# EasyEDA_Pro_EXPORT.net
KiCad netlist of a schematic drawn in EasyEDA Pro
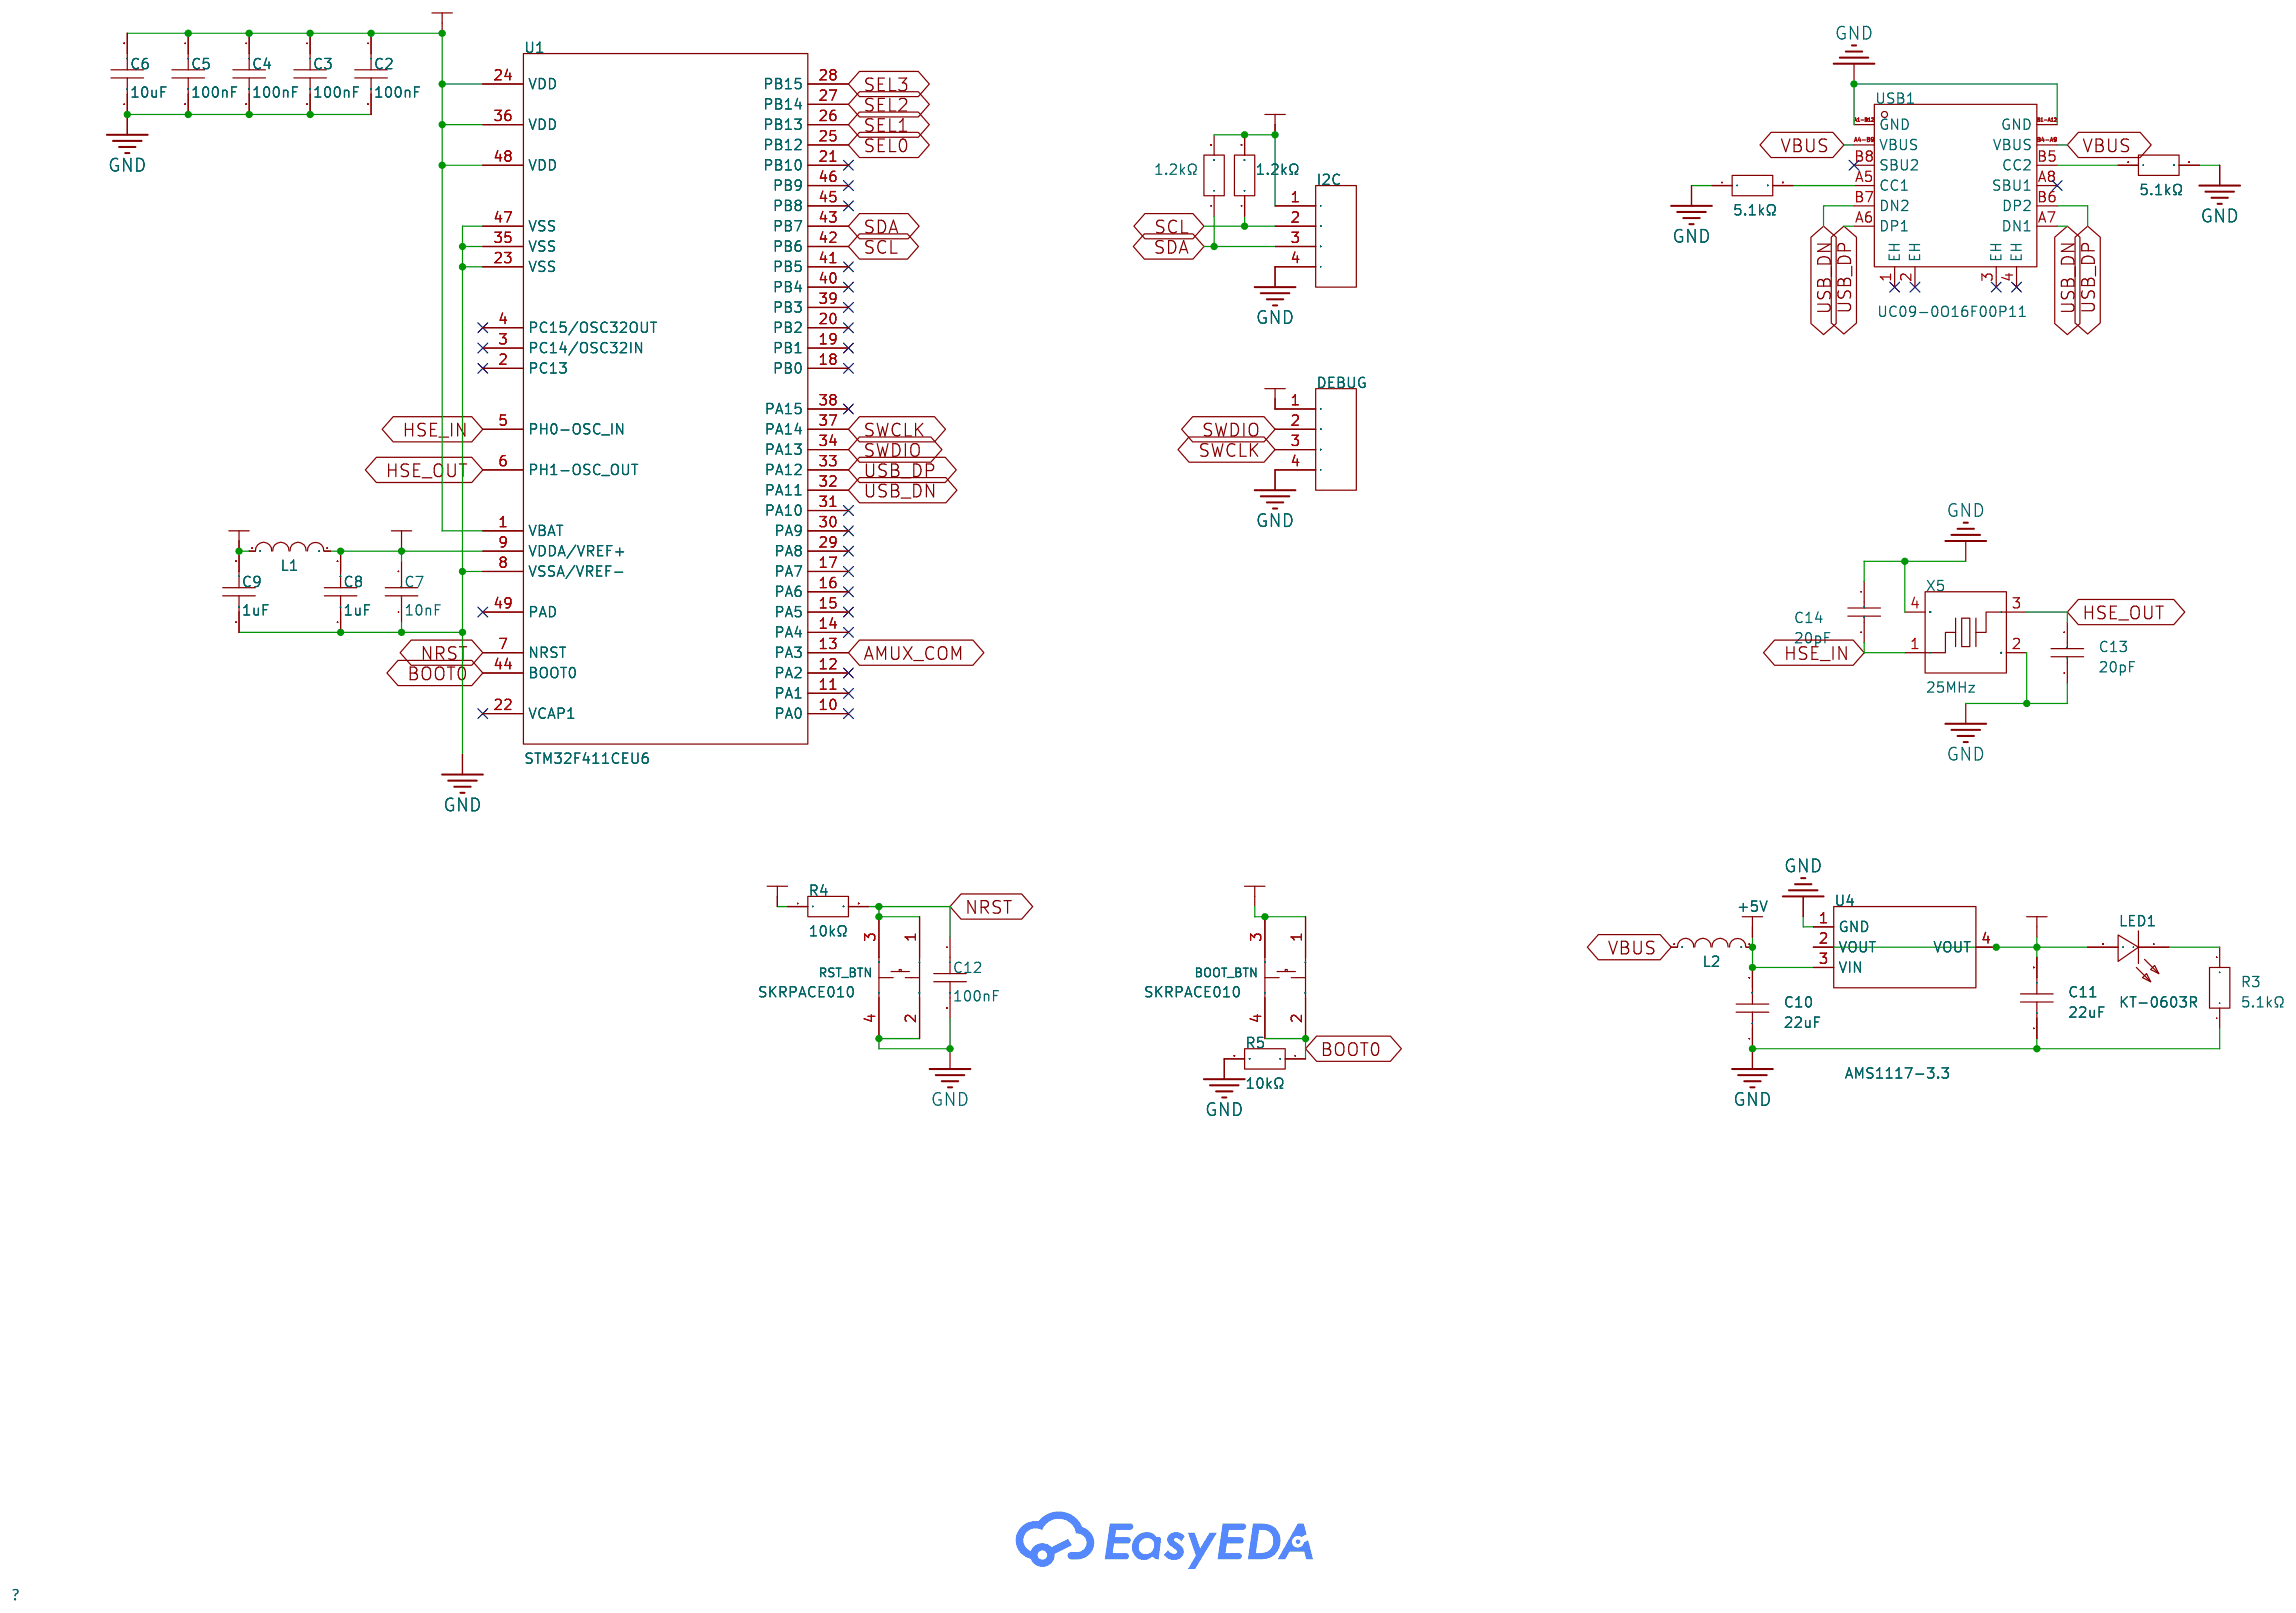
[diagram p0: microcontroller]
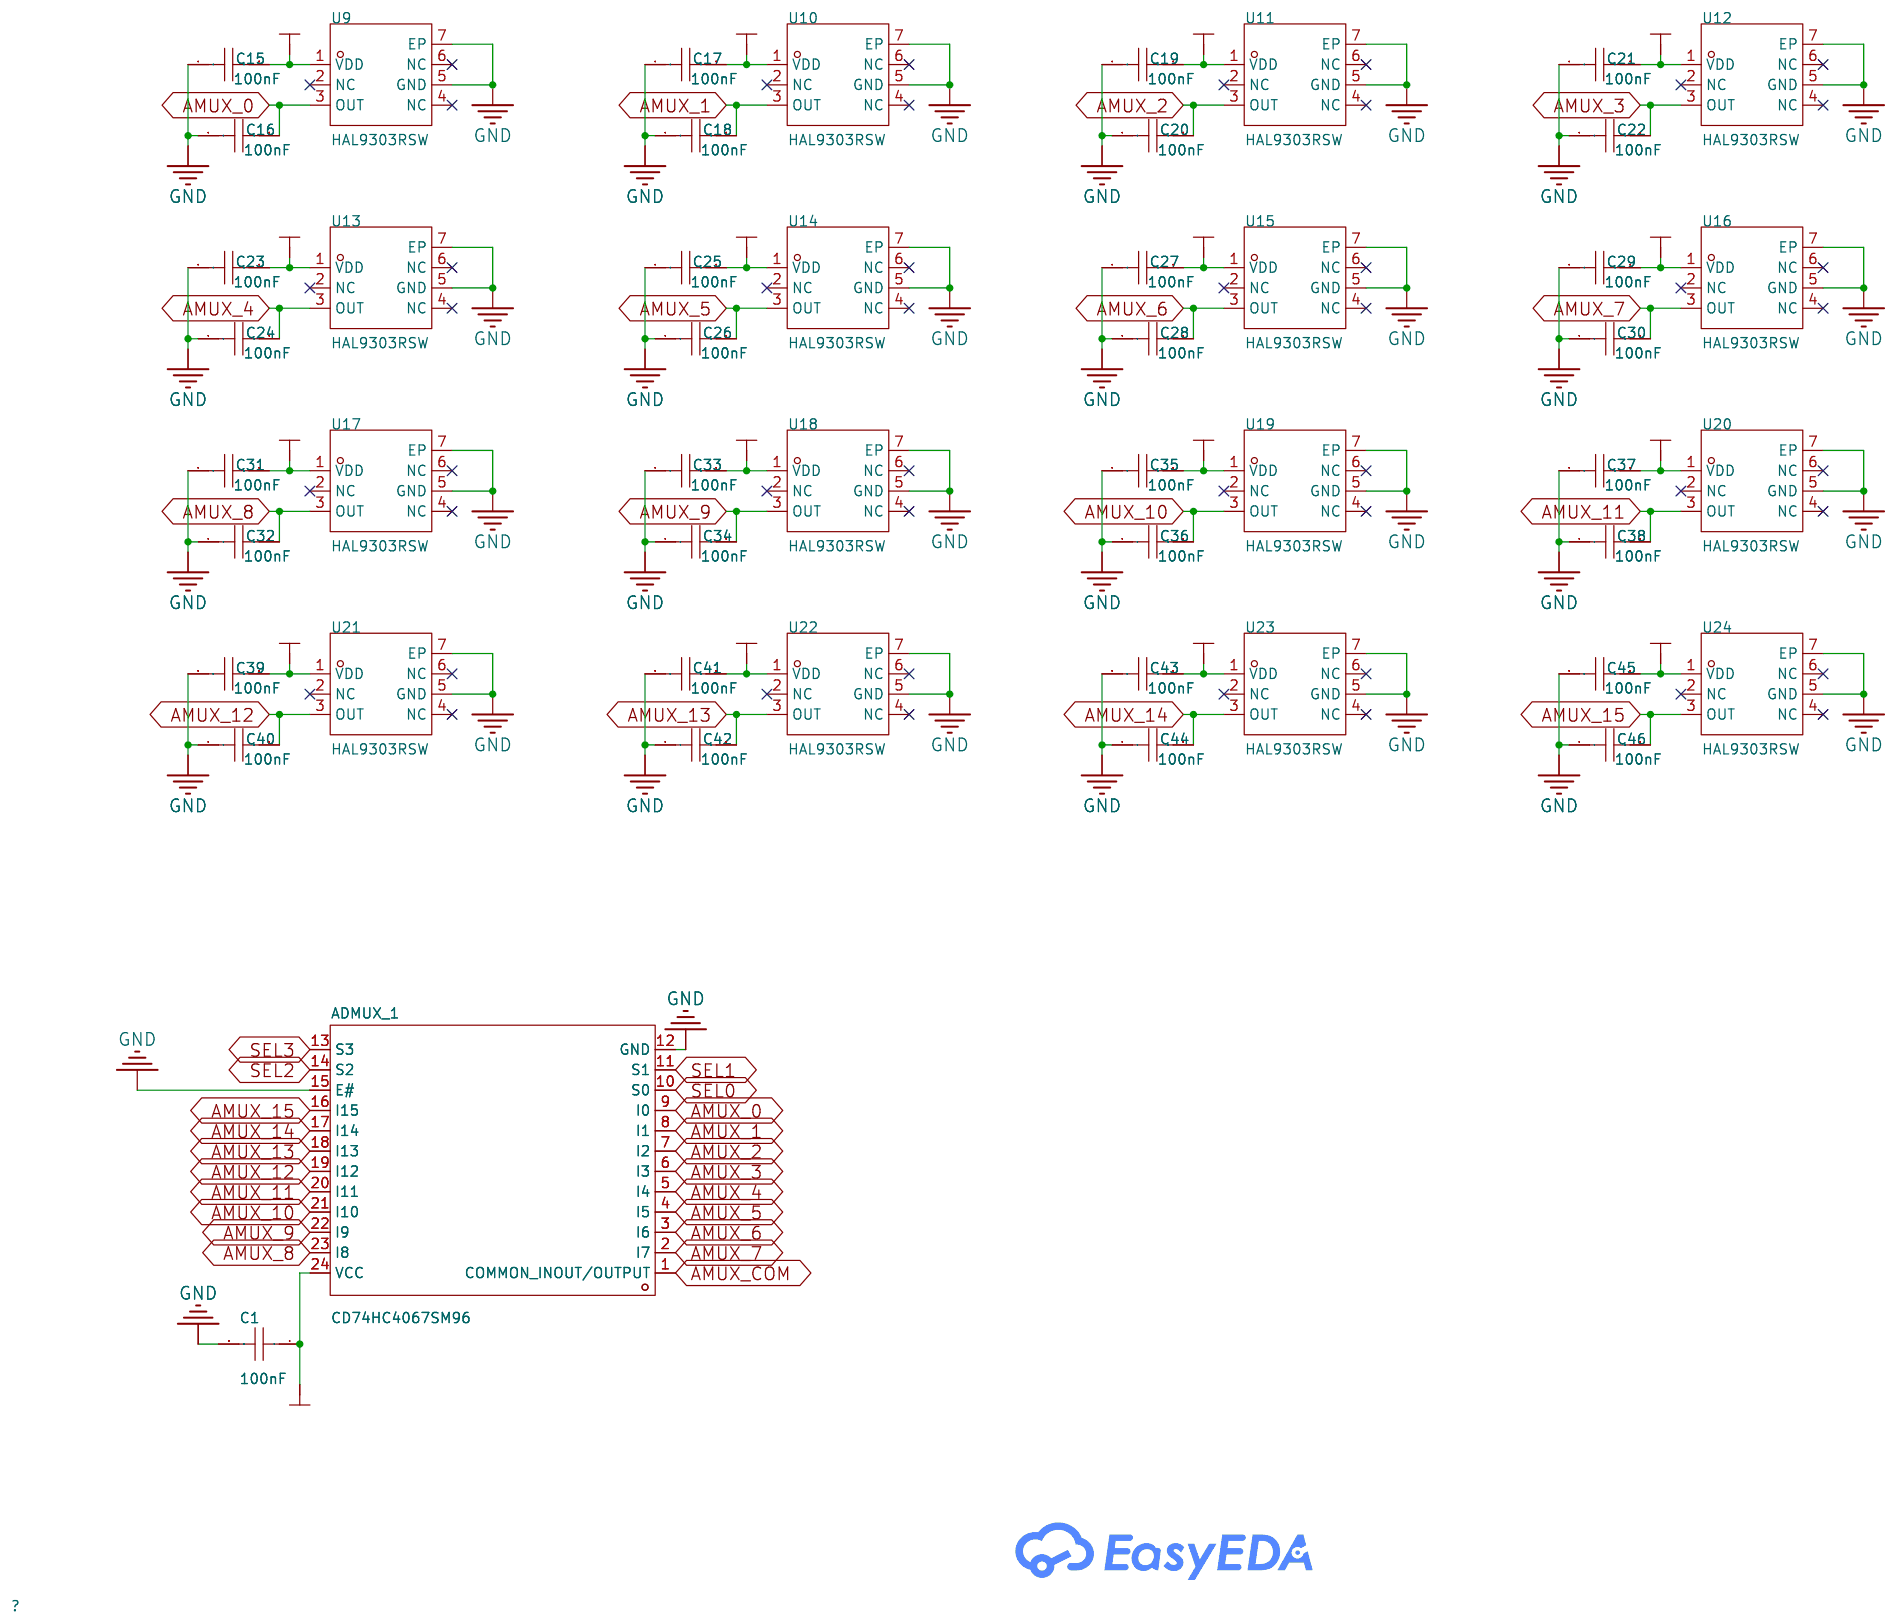
[diagram p1: buttons]

(export (version "E")
  (design (tool "Eeschema 10.0.6"))
  (components
    (comp (ref "BOOT_BTN")
      (value "SKRPACE010")
      (footprint "easyedapro:KEY-SMD_4P-L4.2-W3.2-P2.20-LS4.6")
      (fields (field (name "Manufacturer") "ALPSALPINE(阿尔卑斯阿尔派)"))
      (libsource (lib "easyedapro") (part "SKRPACE010"))
    )
    (comp (ref "C2")
      (value "100nF")
      (footprint "easyedapro:C0201")
      (description "Capacitance:100nF Tolerance:±10% Tolerance:±10% Voltage Rating:16V Temperature Coefficient:X7R")
      (fields
        (field (name "Manufacturer Part") "TCC0201X7R104K160ZT")
        (field (name "Manufacturer") "CCTC(三环)")
      )
      (libsource (lib "easyedapro") (part "TCC0201X7R104K160ZT"))
    )
    (comp (ref "C3")
      (value "100nF")
      (footprint "easyedapro:C0201")
      (description "Capacitance:100nF Tolerance:±10% Tolerance:±10% Voltage Rating:16V Temperature Coefficient:X7R")
      (fields
        (field (name "Manufacturer Part") "TCC0201X7R104K160ZT")
        (field (name "Manufacturer") "CCTC(三环)")
      )
      (libsource (lib "easyedapro") (part "TCC0201X7R104K160ZT"))
    )
    (comp (ref "C4")
      (value "100nF")
      (footprint "easyedapro:C0201")
      (description "Capacitance:100nF Tolerance:±10% Tolerance:±10% Voltage Rating:16V Temperature Coefficient:X7R")
      (fields
        (field (name "Manufacturer Part") "TCC0201X7R104K160ZT")
        (field (name "Manufacturer") "CCTC(三环)")
      )
      (libsource (lib "easyedapro") (part "TCC0201X7R104K160ZT"))
    )
    (comp (ref "C5")
      (value "100nF")
      (footprint "easyedapro:C0201")
      (description "Capacitance:100nF Tolerance:±10% Tolerance:±10% Voltage Rating:16V Temperature Coefficient:X7R")
      (fields
        (field (name "Manufacturer Part") "TCC0201X7R104K160ZT")
        (field (name "Manufacturer") "CCTC(三环)")
      )
      (libsource (lib "easyedapro") (part "TCC0201X7R104K160ZT"))
    )
    (comp (ref "C6")
      (value "10uF")
      (footprint "easyedapro:C1206")
      (description "Capacitance:10uF Tolerance:±10% Tolerance:±10% Voltage Rating:35V Temperature Coefficient:X7R")
      (fields
        (field (name "Manufacturer Part") "HGC1206R7106K350NSPJ")
        (field (name "Manufacturer") "Chinocera(华瓷)")
      )
      (libsource (lib "easyedapro") (part "HGC1206R7106K350NSPJ"))
    )
    (comp (ref "C7")
      (value "10nF")
      (footprint "easyedapro:C0402")
      (description "Capacitance:10nF Tolerance:±10% Tolerance:±10% Voltage Rating:50V Temperature Coefficient:X7R")
      (fields (field (name "Manufacturer Part") "0402B103K500NT") (field (name "Manufacturer") "FH(风华)"))
      (libsource (lib "easyedapro") (part "0402B103K500NT"))
    )
    (comp (ref "C8")
      (value "1uF")
      (footprint "easyedapro:C0402")
      (description "Capacitance:1uF Tolerance:±10% Tolerance:±10% Voltage Rating:50V Temperature Coefficient:X5R")
      (fields
        (field (name "Manufacturer Part") "TCC0402X5R105K500AT")
        (field (name "Manufacturer") "CCTC(三环)")
      )
      (libsource (lib "easyedapro") (part "TCC0402X5R105K500AT"))
    )
    (comp (ref "C9")
      (value "1uF")
      (footprint "easyedapro:C0402")
      (description "Capacitance:1uF Tolerance:±10% Tolerance:±10% Voltage Rating:50V Temperature Coefficient:X5R")
      (fields
        (field (name "Manufacturer Part") "TCC0402X5R105K500AT")
        (field (name "Manufacturer") "CCTC(三环)")
      )
      (libsource (lib "easyedapro") (part "TCC0402X5R105K500AT"))
    )
    (comp (ref "C10")
      (value "22uF")
      (footprint "easyedapro:C1206")
      (description "Capacitance:22uF Tolerance:±10% Tolerance:±10% Voltage Rating:16V Temperature Coefficient:X7R")
      (fields
        (field (name "Manufacturer Part") "TCC1206X7R226K160HT")
        (field (name "Manufacturer") "CCTC(三环)")
      )
      (libsource (lib "easyedapro") (part "TCC1206X7R226K160HT"))
    )
    (comp (ref "C11")
      (value "22uF")
      (footprint "easyedapro:C1206")
      (description "Capacitance:22uF Tolerance:±10% Tolerance:±10% Voltage Rating:16V Temperature Coefficient:X7R")
      (fields
        (field (name "Manufacturer Part") "TCC1206X7R226K160HT")
        (field (name "Manufacturer") "CCTC(三环)")
      )
      (libsource (lib "easyedapro") (part "TCC1206X7R226K160HT"))
    )
    (comp (ref "C12")
      (value "100nF")
      (footprint "easyedapro:C0201")
      (description "Capacitance:100nF Tolerance:±10% Tolerance:±10% Voltage Rating:16V Temperature Coefficient:X7R")
      (fields
        (field (name "Manufacturer Part") "TCC0201X7R104K160ZT")
        (field (name "Manufacturer") "CCTC(三环)")
      )
      (libsource (lib "easyedapro") (part "TCC0201X7R104K160ZT"))
    )
    (comp (ref "C13")
      (value "20pF")
      (footprint "easyedapro:C0402")
      (fields (field (name "Manufacturer Part") "0402CG200J500NT") (field (name "Manufacturer") "FH(风华)"))
      (libsource (lib "easyedapro") (part "0402CG200J500NT"))
    )
    (comp (ref "C14")
      (value "20pF")
      (footprint "easyedapro:C0402")
      (fields (field (name "Manufacturer Part") "0402CG200J500NT") (field (name "Manufacturer") "FH(风华)"))
      (libsource (lib "easyedapro") (part "0402CG200J500NT"))
    )
    (comp (ref "DEBUG")
      (value "~")
      (footprint "easyedapro:4 Pin Header")
      (libsource (lib "easyedapro") (part "4 Pin Header"))
    )
    (comp (ref "I2C")
      (value "~")
      (footprint "easyedapro:4 Pin Header")
      (libsource (lib "easyedapro") (part "4 Pin Header"))
    )
    (comp (ref "L1")
      (value "BLM18AG121SN1D")
      (footprint "easyedapro:L0603")
      (fields (field (name "Manufacturer") "muRata(村田)"))
      (libsource (lib "easyedapro") (part "BLM18AG121SN1D"))
    )
    (comp (ref "L2")
      (value "BLM18AG121SN1D")
      (footprint "easyedapro:L0603")
      (fields (field (name "Manufacturer") "muRata(村田)"))
      (libsource (lib "easyedapro") (part "BLM18AG121SN1D"))
    )
    (comp (ref "LED1")
      (value "KT-0603R")
      (footprint "easyedapro:LED0603-RD")
      (fields (field (name "Manufacturer") "KENTO"))
      (libsource (lib "easyedapro") (part "KT-0603R"))
    )
    (comp (ref "R1")
      (value "5.1kΩ")
      (footprint "easyedapro:R0402")
      (fields (field (name "Manufacturer Part") "FRC0402J512 TS") (field (name "Manufacturer") "FOJAN(富捷)"))
      (libsource (lib "easyedapro") (part "FRC0402J512 TS"))
    )
    (comp (ref "R2")
      (value "5.1kΩ")
      (footprint "easyedapro:R0402")
      (fields (field (name "Manufacturer Part") "FRC0402J512 TS") (field (name "Manufacturer") "FOJAN(富捷)"))
      (libsource (lib "easyedapro") (part "FRC0402J512 TS"))
    )
    (comp (ref "R3")
      (value "5.1kΩ")
      (footprint "easyedapro:R0402")
      (fields (field (name "Manufacturer Part") "FRC0402J512 TS") (field (name "Manufacturer") "FOJAN(富捷)"))
      (libsource (lib "easyedapro") (part "FRC0402J512 TS"))
    )
    (comp (ref "R4")
      (value "10kΩ")
      (footprint "easyedapro:R0805")
      (fields
        (field (name "Manufacturer Part") "HoAR0805-1/8W-10KR-1%-TCR25")
        (field (name "Manufacturer") "Milliohm(毫欧)")
      )
      (libsource (lib "easyedapro") (part "HOAR0805-1/8W-10KR-1%-TCR25"))
    )
    (comp (ref "R5")
      (value "10kΩ")
      (footprint "easyedapro:R0805")
      (fields
        (field (name "Manufacturer Part") "HoAR0805-1/8W-10KR-1%-TCR25")
        (field (name "Manufacturer") "Milliohm(毫欧)")
      )
      (libsource (lib "easyedapro") (part "HOAR0805-1/8W-10KR-1%-TCR25"))
    )
    (comp (ref "R6")
      (value "1.2kΩ")
      (footprint "easyedapro:R0201")
      (fields (field (name "Manufacturer Part") "AC0201FR-071K2L") (field (name "Manufacturer") "YAGEO(国巨)"))
      (libsource (lib "easyedapro") (part "AC0201FR-071K2L"))
    )
    (comp (ref "R7")
      (value "1.2kΩ")
      (footprint "easyedapro:R0201")
      (fields (field (name "Manufacturer Part") "AC0201FR-071K2L") (field (name "Manufacturer") "YAGEO(国巨)"))
      (libsource (lib "easyedapro") (part "AC0201FR-071K2L"))
    )
    (comp (ref "RST_BTN")
      (value "SKRPACE010")
      (footprint "easyedapro:KEY-SMD_4P-L4.2-W3.2-P2.20-LS4.6")
      (fields (field (name "Manufacturer") "ALPSALPINE(阿尔卑斯阿尔派)"))
      (libsource (lib "easyedapro") (part "SKRPACE010"))
    )
    (comp (ref "U1")
      (value "STM32F411CEU6")
      (footprint "easyedapro:UFQFPN-48_L7.0-W7.0-P0.50-BL-EP")
      (fields (field (name "Manufacturer") "ST(意法半导体)"))
      (libsource (lib "easyedapro") (part "STM32F411CEU6"))
    )
    (comp (ref "U4")
      (value "AMS1117-3.3")
      (footprint "easyedapro:SOT-223-3_L6.5-W3.4-P2.30-LS7.0-BR")
      (fields (field (name "Manufacturer") "AMS"))
      (libsource (lib "easyedapro") (part "AMS1117-3.3"))
    )
    (comp (ref "USB1")
      (value "UC09-0O16F00P11")
      (footprint "easyedapro:USB-C-SMD_UC09-0O16F00P11")
      (fields (field (name "Manufacturer") "BXCONN(宝讯)"))
      (libsource (lib "easyedapro") (part "UC09-0O16F00P11"))
    )
    (comp (ref "X5")
      (value "25MHz")
      (footprint "easyedapro:CRYSTAL-SMD_4P-L3.2-W2.5-BL")
      (fields (field (name "Manufacturer Part") "S3225000271060C3") (field (name "Manufacturer") "JGHC(晶光华)"))
      (libsource (lib "easyedapro") (part "S3225000271060C3"))
    )
    (comp (ref "ADMUX_1")
      (value "CD74HC4067SM96")
      (footprint "easyedapro:SSOP-24_L8.1-W5.3-P0.65-LS7.8-BL")
      (fields (field (name "Manufacturer") "TI(德州仪器)"))
      (libsource (lib "easyedapro") (part "CD74HC4067SM96"))
    )
    (comp (ref "C1")
      (value "100nF")
      (footprint "easyedapro:C0201")
      (description "Capacitance:100nF Tolerance:±10% Tolerance:±10% Voltage Rating:16V Temperature Coefficient:X7R")
      (fields
        (field (name "Manufacturer Part") "TCC0201X7R104K160ZT")
        (field (name "Manufacturer") "CCTC(三环)")
      )
      (libsource (lib "easyedapro") (part "TCC0201X7R104K160ZT"))
    )
    (comp (ref "C15")
      (value "100nF")
      (footprint "easyedapro:C0201")
      (description "Capacitance:100nF Tolerance:±10% Tolerance:±10% Voltage Rating:16V Temperature Coefficient:X7R")
      (fields
        (field (name "Manufacturer Part") "TCC0201X7R104K160ZT")
        (field (name "Manufacturer") "CCTC(三环)")
      )
      (libsource (lib "easyedapro") (part "TCC0201X7R104K160ZT"))
    )
    (comp (ref "C16")
      (value "100nF")
      (footprint "easyedapro:C0201")
      (description "Capacitance:100nF Tolerance:±10% Tolerance:±10% Voltage Rating:16V Temperature Coefficient:X7R")
      (fields
        (field (name "Manufacturer Part") "TCC0201X7R104K160ZT")
        (field (name "Manufacturer") "CCTC(三环)")
      )
      (libsource (lib "easyedapro") (part "TCC0201X7R104K160ZT"))
    )
    (comp (ref "C17")
      (value "100nF")
      (footprint "easyedapro:C0201")
      (description "Capacitance:100nF Tolerance:±10% Tolerance:±10% Voltage Rating:16V Temperature Coefficient:X7R")
      (fields
        (field (name "Manufacturer Part") "TCC0201X7R104K160ZT")
        (field (name "Manufacturer") "CCTC(三环)")
      )
      (libsource (lib "easyedapro") (part "TCC0201X7R104K160ZT"))
    )
    (comp (ref "C18")
      (value "100nF")
      (footprint "easyedapro:C0201")
      (description "Capacitance:100nF Tolerance:±10% Tolerance:±10% Voltage Rating:16V Temperature Coefficient:X7R")
      (fields
        (field (name "Manufacturer Part") "TCC0201X7R104K160ZT")
        (field (name "Manufacturer") "CCTC(三环)")
      )
      (libsource (lib "easyedapro") (part "TCC0201X7R104K160ZT"))
    )
    (comp (ref "C19")
      (value "100nF")
      (footprint "easyedapro:C0201")
      (description "Capacitance:100nF Tolerance:±10% Tolerance:±10% Voltage Rating:16V Temperature Coefficient:X7R")
      (fields
        (field (name "Manufacturer Part") "TCC0201X7R104K160ZT")
        (field (name "Manufacturer") "CCTC(三环)")
      )
      (libsource (lib "easyedapro") (part "TCC0201X7R104K160ZT"))
    )
    (comp (ref "C20")
      (value "100nF")
      (footprint "easyedapro:C0201")
      (description "Capacitance:100nF Tolerance:±10% Tolerance:±10% Voltage Rating:16V Temperature Coefficient:X7R")
      (fields
        (field (name "Manufacturer Part") "TCC0201X7R104K160ZT")
        (field (name "Manufacturer") "CCTC(三环)")
      )
      (libsource (lib "easyedapro") (part "TCC0201X7R104K160ZT"))
    )
    (comp (ref "C21")
      (value "100nF")
      (footprint "easyedapro:C0201")
      (description "Capacitance:100nF Tolerance:±10% Tolerance:±10% Voltage Rating:16V Temperature Coefficient:X7R")
      (fields
        (field (name "Manufacturer Part") "TCC0201X7R104K160ZT")
        (field (name "Manufacturer") "CCTC(三环)")
      )
      (libsource (lib "easyedapro") (part "TCC0201X7R104K160ZT"))
    )
    (comp (ref "C22")
      (value "100nF")
      (footprint "easyedapro:C0201")
      (description "Capacitance:100nF Tolerance:±10% Tolerance:±10% Voltage Rating:16V Temperature Coefficient:X7R")
      (fields
        (field (name "Manufacturer Part") "TCC0201X7R104K160ZT")
        (field (name "Manufacturer") "CCTC(三环)")
      )
      (libsource (lib "easyedapro") (part "TCC0201X7R104K160ZT"))
    )
    (comp (ref "C23")
      (value "100nF")
      (footprint "easyedapro:C0201")
      (description "Capacitance:100nF Tolerance:±10% Tolerance:±10% Voltage Rating:16V Temperature Coefficient:X7R")
      (fields
        (field (name "Manufacturer Part") "TCC0201X7R104K160ZT")
        (field (name "Manufacturer") "CCTC(三环)")
      )
      (libsource (lib "easyedapro") (part "TCC0201X7R104K160ZT"))
    )
    (comp (ref "C24")
      (value "100nF")
      (footprint "easyedapro:C0201")
      (description "Capacitance:100nF Tolerance:±10% Tolerance:±10% Voltage Rating:16V Temperature Coefficient:X7R")
      (fields
        (field (name "Manufacturer Part") "TCC0201X7R104K160ZT")
        (field (name "Manufacturer") "CCTC(三环)")
      )
      (libsource (lib "easyedapro") (part "TCC0201X7R104K160ZT"))
    )
    (comp (ref "C25")
      (value "100nF")
      (footprint "easyedapro:C0201")
      (description "Capacitance:100nF Tolerance:±10% Tolerance:±10% Voltage Rating:16V Temperature Coefficient:X7R")
      (fields
        (field (name "Manufacturer Part") "TCC0201X7R104K160ZT")
        (field (name "Manufacturer") "CCTC(三环)")
      )
      (libsource (lib "easyedapro") (part "TCC0201X7R104K160ZT"))
    )
    (comp (ref "C26")
      (value "100nF")
      (footprint "easyedapro:C0201")
      (description "Capacitance:100nF Tolerance:±10% Tolerance:±10% Voltage Rating:16V Temperature Coefficient:X7R")
      (fields
        (field (name "Manufacturer Part") "TCC0201X7R104K160ZT")
        (field (name "Manufacturer") "CCTC(三环)")
      )
      (libsource (lib "easyedapro") (part "TCC0201X7R104K160ZT"))
    )
    (comp (ref "C27")
      (value "100nF")
      (footprint "easyedapro:C0201")
      (description "Capacitance:100nF Tolerance:±10% Tolerance:±10% Voltage Rating:16V Temperature Coefficient:X7R")
      (fields
        (field (name "Manufacturer Part") "TCC0201X7R104K160ZT")
        (field (name "Manufacturer") "CCTC(三环)")
      )
      (libsource (lib "easyedapro") (part "TCC0201X7R104K160ZT"))
    )
    (comp (ref "C28")
      (value "100nF")
      (footprint "easyedapro:C0201")
      (description "Capacitance:100nF Tolerance:±10% Tolerance:±10% Voltage Rating:16V Temperature Coefficient:X7R")
      (fields
        (field (name "Manufacturer Part") "TCC0201X7R104K160ZT")
        (field (name "Manufacturer") "CCTC(三环)")
      )
      (libsource (lib "easyedapro") (part "TCC0201X7R104K160ZT"))
    )
    (comp (ref "C29")
      (value "100nF")
      (footprint "easyedapro:C0201")
      (description "Capacitance:100nF Tolerance:±10% Tolerance:±10% Voltage Rating:16V Temperature Coefficient:X7R")
      (fields
        (field (name "Manufacturer Part") "TCC0201X7R104K160ZT")
        (field (name "Manufacturer") "CCTC(三环)")
      )
      (libsource (lib "easyedapro") (part "TCC0201X7R104K160ZT"))
    )
    (comp (ref "C30")
      (value "100nF")
      (footprint "easyedapro:C0201")
      (description "Capacitance:100nF Tolerance:±10% Tolerance:±10% Voltage Rating:16V Temperature Coefficient:X7R")
      (fields
        (field (name "Manufacturer Part") "TCC0201X7R104K160ZT")
        (field (name "Manufacturer") "CCTC(三环)")
      )
      (libsource (lib "easyedapro") (part "TCC0201X7R104K160ZT"))
    )
    (comp (ref "C31")
      (value "100nF")
      (footprint "easyedapro:C0201")
      (description "Capacitance:100nF Tolerance:±10% Tolerance:±10% Voltage Rating:16V Temperature Coefficient:X7R")
      (fields
        (field (name "Manufacturer Part") "TCC0201X7R104K160ZT")
        (field (name "Manufacturer") "CCTC(三环)")
      )
      (libsource (lib "easyedapro") (part "TCC0201X7R104K160ZT"))
    )
    (comp (ref "C32")
      (value "100nF")
      (footprint "easyedapro:C0201")
      (description "Capacitance:100nF Tolerance:±10% Tolerance:±10% Voltage Rating:16V Temperature Coefficient:X7R")
      (fields
        (field (name "Manufacturer Part") "TCC0201X7R104K160ZT")
        (field (name "Manufacturer") "CCTC(三环)")
      )
      (libsource (lib "easyedapro") (part "TCC0201X7R104K160ZT"))
    )
    (comp (ref "C33")
      (value "100nF")
      (footprint "easyedapro:C0201")
      (description "Capacitance:100nF Tolerance:±10% Tolerance:±10% Voltage Rating:16V Temperature Coefficient:X7R")
      (fields
        (field (name "Manufacturer Part") "TCC0201X7R104K160ZT")
        (field (name "Manufacturer") "CCTC(三环)")
      )
      (libsource (lib "easyedapro") (part "TCC0201X7R104K160ZT"))
    )
    (comp (ref "C34")
      (value "100nF")
      (footprint "easyedapro:C0201")
      (description "Capacitance:100nF Tolerance:±10% Tolerance:±10% Voltage Rating:16V Temperature Coefficient:X7R")
      (fields
        (field (name "Manufacturer Part") "TCC0201X7R104K160ZT")
        (field (name "Manufacturer") "CCTC(三环)")
      )
      (libsource (lib "easyedapro") (part "TCC0201X7R104K160ZT"))
    )
    (comp (ref "C35")
      (value "100nF")
      (footprint "easyedapro:C0201")
      (description "Capacitance:100nF Tolerance:±10% Tolerance:±10% Voltage Rating:16V Temperature Coefficient:X7R")
      (fields
        (field (name "Manufacturer Part") "TCC0201X7R104K160ZT")
        (field (name "Manufacturer") "CCTC(三环)")
      )
      (libsource (lib "easyedapro") (part "TCC0201X7R104K160ZT"))
    )
    (comp (ref "C36")
      (value "100nF")
      (footprint "easyedapro:C0201")
      (description "Capacitance:100nF Tolerance:±10% Tolerance:±10% Voltage Rating:16V Temperature Coefficient:X7R")
      (fields
        (field (name "Manufacturer Part") "TCC0201X7R104K160ZT")
        (field (name "Manufacturer") "CCTC(三环)")
      )
      (libsource (lib "easyedapro") (part "TCC0201X7R104K160ZT"))
    )
    (comp (ref "C37")
      (value "100nF")
      (footprint "easyedapro:C0201")
      (description "Capacitance:100nF Tolerance:±10% Tolerance:±10% Voltage Rating:16V Temperature Coefficient:X7R")
      (fields
        (field (name "Manufacturer Part") "TCC0201X7R104K160ZT")
        (field (name "Manufacturer") "CCTC(三环)")
      )
      (libsource (lib "easyedapro") (part "TCC0201X7R104K160ZT"))
    )
    (comp (ref "C38")
      (value "100nF")
      (footprint "easyedapro:C0201")
      (description "Capacitance:100nF Tolerance:±10% Tolerance:±10% Voltage Rating:16V Temperature Coefficient:X7R")
      (fields
        (field (name "Manufacturer Part") "TCC0201X7R104K160ZT")
        (field (name "Manufacturer") "CCTC(三环)")
      )
      (libsource (lib "easyedapro") (part "TCC0201X7R104K160ZT"))
    )
    (comp (ref "C39")
      (value "100nF")
      (footprint "easyedapro:C0201")
      (description "Capacitance:100nF Tolerance:±10% Tolerance:±10% Voltage Rating:16V Temperature Coefficient:X7R")
      (fields
        (field (name "Manufacturer Part") "TCC0201X7R104K160ZT")
        (field (name "Manufacturer") "CCTC(三环)")
      )
      (libsource (lib "easyedapro") (part "TCC0201X7R104K160ZT"))
    )
    (comp (ref "C40")
      (value "100nF")
      (footprint "easyedapro:C0201")
      (description "Capacitance:100nF Tolerance:±10% Tolerance:±10% Voltage Rating:16V Temperature Coefficient:X7R")
      (fields
        (field (name "Manufacturer Part") "TCC0201X7R104K160ZT")
        (field (name "Manufacturer") "CCTC(三环)")
      )
      (libsource (lib "easyedapro") (part "TCC0201X7R104K160ZT"))
    )
    (comp (ref "C41")
      (value "100nF")
      (footprint "easyedapro:C0201")
      (description "Capacitance:100nF Tolerance:±10% Tolerance:±10% Voltage Rating:16V Temperature Coefficient:X7R")
      (fields
        (field (name "Manufacturer Part") "TCC0201X7R104K160ZT")
        (field (name "Manufacturer") "CCTC(三环)")
      )
      (libsource (lib "easyedapro") (part "TCC0201X7R104K160ZT"))
    )
    (comp (ref "C42")
      (value "100nF")
      (footprint "easyedapro:C0201")
      (description "Capacitance:100nF Tolerance:±10% Tolerance:±10% Voltage Rating:16V Temperature Coefficient:X7R")
      (fields
        (field (name "Manufacturer Part") "TCC0201X7R104K160ZT")
        (field (name "Manufacturer") "CCTC(三环)")
      )
      (libsource (lib "easyedapro") (part "TCC0201X7R104K160ZT"))
    )
    (comp (ref "C43")
      (value "100nF")
      (footprint "easyedapro:C0201")
      (description "Capacitance:100nF Tolerance:±10% Tolerance:±10% Voltage Rating:16V Temperature Coefficient:X7R")
      (fields
        (field (name "Manufacturer Part") "TCC0201X7R104K160ZT")
        (field (name "Manufacturer") "CCTC(三环)")
      )
      (libsource (lib "easyedapro") (part "TCC0201X7R104K160ZT"))
    )
    (comp (ref "C44")
      (value "100nF")
      (footprint "easyedapro:C0201")
      (description "Capacitance:100nF Tolerance:±10% Tolerance:±10% Voltage Rating:16V Temperature Coefficient:X7R")
      (fields
        (field (name "Manufacturer Part") "TCC0201X7R104K160ZT")
        (field (name "Manufacturer") "CCTC(三环)")
      )
      (libsource (lib "easyedapro") (part "TCC0201X7R104K160ZT"))
    )
    (comp (ref "C45")
      (value "100nF")
      (footprint "easyedapro:C0201")
      (description "Capacitance:100nF Tolerance:±10% Tolerance:±10% Voltage Rating:16V Temperature Coefficient:X7R")
      (fields
        (field (name "Manufacturer Part") "TCC0201X7R104K160ZT")
        (field (name "Manufacturer") "CCTC(三环)")
      )
      (libsource (lib "easyedapro") (part "TCC0201X7R104K160ZT"))
    )
    (comp (ref "C46")
      (value "100nF")
      (footprint "easyedapro:C0201")
      (description "Capacitance:100nF Tolerance:±10% Tolerance:±10% Voltage Rating:16V Temperature Coefficient:X7R")
      (fields
        (field (name "Manufacturer Part") "TCC0201X7R104K160ZT")
        (field (name "Manufacturer") "CCTC(三环)")
      )
      (libsource (lib "easyedapro") (part "TCC0201X7R104K160ZT"))
    )
    (comp (ref "U9")
      (value "HAL9303RSW")
      (footprint "easyedapro:DFN1616-6_L1.6-W1.6-P0.50-BL-EP_RICOH_RP500X")
      (description "Type:- supply voltage:- supply voltage:-")
      (fields (field (name "Manufacturer") "Hallwee(霍尔微电子)"))
      (libsource (lib "easyedapro") (part "HAL9303RSW"))
    )
    (comp (ref "U10")
      (value "HAL9303RSW")
      (footprint "easyedapro:DFN1616-6_L1.6-W1.6-P0.50-BL-EP_RICOH_RP500X")
      (description "Type:- supply voltage:- supply voltage:-")
      (fields (field (name "Manufacturer") "Hallwee(霍尔微电子)"))
      (libsource (lib "easyedapro") (part "HAL9303RSW"))
    )
    (comp (ref "U11")
      (value "HAL9303RSW")
      (footprint "easyedapro:DFN1616-6_L1.6-W1.6-P0.50-BL-EP_RICOH_RP500X")
      (description "Type:- supply voltage:- supply voltage:-")
      (fields (field (name "Manufacturer") "Hallwee(霍尔微电子)"))
      (libsource (lib "easyedapro") (part "HAL9303RSW"))
    )
    (comp (ref "U12")
      (value "HAL9303RSW")
      (footprint "easyedapro:DFN1616-6_L1.6-W1.6-P0.50-BL-EP_RICOH_RP500X")
      (description "Type:- supply voltage:- supply voltage:-")
      (fields (field (name "Manufacturer") "Hallwee(霍尔微电子)"))
      (libsource (lib "easyedapro") (part "HAL9303RSW"))
    )
    (comp (ref "U13")
      (value "HAL9303RSW")
      (footprint "easyedapro:DFN1616-6_L1.6-W1.6-P0.50-BL-EP_RICOH_RP500X")
      (description "Type:- supply voltage:- supply voltage:-")
      (fields (field (name "Manufacturer") "Hallwee(霍尔微电子)"))
      (libsource (lib "easyedapro") (part "HAL9303RSW"))
    )
    (comp (ref "U14")
      (value "HAL9303RSW")
      (footprint "easyedapro:DFN1616-6_L1.6-W1.6-P0.50-BL-EP_RICOH_RP500X")
      (description "Type:- supply voltage:- supply voltage:-")
      (fields (field (name "Manufacturer") "Hallwee(霍尔微电子)"))
      (libsource (lib "easyedapro") (part "HAL9303RSW"))
    )
    (comp (ref "U15")
      (value "HAL9303RSW")
      (footprint "easyedapro:DFN1616-6_L1.6-W1.6-P0.50-BL-EP_RICOH_RP500X")
      (description "Type:- supply voltage:- supply voltage:-")
      (fields (field (name "Manufacturer") "Hallwee(霍尔微电子)"))
      (libsource (lib "easyedapro") (part "HAL9303RSW"))
    )
    (comp (ref "U16")
      (value "HAL9303RSW")
      (footprint "easyedapro:DFN1616-6_L1.6-W1.6-P0.50-BL-EP_RICOH_RP500X")
      (description "Type:- supply voltage:- supply voltage:-")
      (fields (field (name "Manufacturer") "Hallwee(霍尔微电子)"))
      (libsource (lib "easyedapro") (part "HAL9303RSW"))
    )
    (comp (ref "U17")
      (value "HAL9303RSW")
      (footprint "easyedapro:DFN1616-6_L1.6-W1.6-P0.50-BL-EP_RICOH_RP500X")
      (description "Type:- supply voltage:- supply voltage:-")
      (fields (field (name "Manufacturer") "Hallwee(霍尔微电子)"))
      (libsource (lib "easyedapro") (part "HAL9303RSW"))
    )
    (comp (ref "U18")
      (value "HAL9303RSW")
      (footprint "easyedapro:DFN1616-6_L1.6-W1.6-P0.50-BL-EP_RICOH_RP500X")
      (description "Type:- supply voltage:- supply voltage:-")
      (fields (field (name "Manufacturer") "Hallwee(霍尔微电子)"))
      (libsource (lib "easyedapro") (part "HAL9303RSW"))
    )
    (comp (ref "U19")
      (value "HAL9303RSW")
      (footprint "easyedapro:DFN1616-6_L1.6-W1.6-P0.50-BL-EP_RICOH_RP500X")
      (description "Type:- supply voltage:- supply voltage:-")
      (fields (field (name "Manufacturer") "Hallwee(霍尔微电子)"))
      (libsource (lib "easyedapro") (part "HAL9303RSW"))
    )
    (comp (ref "U20")
      (value "HAL9303RSW")
      (footprint "easyedapro:DFN1616-6_L1.6-W1.6-P0.50-BL-EP_RICOH_RP500X")
      (description "Type:- supply voltage:- supply voltage:-")
      (fields (field (name "Manufacturer") "Hallwee(霍尔微电子)"))
      (libsource (lib "easyedapro") (part "HAL9303RSW"))
    )
    (comp (ref "U21")
      (value "HAL9303RSW")
      (footprint "easyedapro:DFN1616-6_L1.6-W1.6-P0.50-BL-EP_RICOH_RP500X")
      (description "Type:- supply voltage:- supply voltage:-")
      (fields (field (name "Manufacturer") "Hallwee(霍尔微电子)"))
      (libsource (lib "easyedapro") (part "HAL9303RSW"))
    )
    (comp (ref "U22")
      (value "HAL9303RSW")
      (footprint "easyedapro:DFN1616-6_L1.6-W1.6-P0.50-BL-EP_RICOH_RP500X")
      (description "Type:- supply voltage:- supply voltage:-")
      (fields (field (name "Manufacturer") "Hallwee(霍尔微电子)"))
      (libsource (lib "easyedapro") (part "HAL9303RSW"))
    )
    (comp (ref "U23")
      (value "HAL9303RSW")
      (footprint "easyedapro:DFN1616-6_L1.6-W1.6-P0.50-BL-EP_RICOH_RP500X")
      (description "Type:- supply voltage:- supply voltage:-")
      (fields (field (name "Manufacturer") "Hallwee(霍尔微电子)"))
      (libsource (lib "easyedapro") (part "HAL9303RSW"))
    )
    (comp (ref "U24")
      (value "HAL9303RSW")
      (footprint "easyedapro:DFN1616-6_L1.6-W1.6-P0.50-BL-EP_RICOH_RP500X")
      (description "Type:- supply voltage:- supply voltage:-")
      (fields (field (name "Manufacturer") "Hallwee(霍尔微电子)"))
      (libsource (lib "easyedapro") (part "HAL9303RSW"))
    )
  )
  (nets
    (net (code "1") (name "+3.3V") (class "Default")
      (node (ref "ADMUX_1") (pin "24") (pinfunction "VCC_24") (pintype "unspecified"))
      (node (ref "BOOT_BTN") (pin "1") (pinfunction "1_1") (pintype "input"))
      (node (ref "BOOT_BTN") (pin "3") (pinfunction "3_3") (pintype "input"))
      (node (ref "C1") (pin "1") (pinfunction "1_1") (pintype "unspecified"))
      (node (ref "C11") (pin "2") (pinfunction "2_2") (pintype "unspecified"))
      (node (ref "C15") (pin "2") (pinfunction "2_2") (pintype "unspecified"))
      (node (ref "C17") (pin "2") (pinfunction "2_2") (pintype "unspecified"))
      (node (ref "C19") (pin "2") (pinfunction "2_2") (pintype "unspecified"))
      (node (ref "C2") (pin "1") (pinfunction "1_1") (pintype "unspecified"))
      (node (ref "C21") (pin "2") (pinfunction "2_2") (pintype "unspecified"))
      (node (ref "C23") (pin "2") (pinfunction "2_2") (pintype "unspecified"))
      (node (ref "C25") (pin "2") (pinfunction "2_2") (pintype "unspecified"))
      (node (ref "C27") (pin "2") (pinfunction "2_2") (pintype "unspecified"))
      (node (ref "C29") (pin "2") (pinfunction "2_2") (pintype "unspecified"))
      (node (ref "C3") (pin "1") (pinfunction "1_1") (pintype "unspecified"))
      (node (ref "C31") (pin "2") (pinfunction "2_2") (pintype "unspecified"))
      (node (ref "C33") (pin "2") (pinfunction "2_2") (pintype "unspecified"))
      (node (ref "C35") (pin "2") (pinfunction "2_2") (pintype "unspecified"))
      (node (ref "C37") (pin "2") (pinfunction "2_2") (pintype "unspecified"))
      (node (ref "C39") (pin "2") (pinfunction "2_2") (pintype "unspecified"))
      (node (ref "C4") (pin "1") (pinfunction "1_1") (pintype "unspecified"))
      (node (ref "C41") (pin "2") (pinfunction "2_2") (pintype "unspecified"))
      (node (ref "C43") (pin "2") (pinfunction "2_2") (pintype "unspecified"))
      (node (ref "C45") (pin "2") (pinfunction "2_2") (pintype "unspecified"))
      (node (ref "C5") (pin "1") (pinfunction "1_1") (pintype "unspecified"))
      (node (ref "C6") (pin "2") (pinfunction "2_2") (pintype "unspecified"))
      (node (ref "C9") (pin "2") (pinfunction "2_2") (pintype "unspecified"))
      (node (ref "DEBUG") (pin "1") (pinfunction "1_1") (pintype "input"))
      (node (ref "I2C") (pin "1") (pinfunction "1_1") (pintype "input"))
      (node (ref "L1") (pin "1") (pinfunction "1_1") (pintype "unspecified"))
      (node (ref "LED1") (pin "2") (pinfunction "A_2") (pintype "unspecified"))
      (node (ref "R4") (pin "1") (pinfunction "1_1") (pintype "unspecified"))
      (node (ref "R6") (pin "2") (pinfunction "2_2") (pintype "unspecified"))
      (node (ref "R7") (pin "2") (pinfunction "2_2") (pintype "unspecified"))
      (node (ref "U1") (pin "1") (pinfunction "VBAT_1") (pintype "unspecified"))
      (node (ref "U1") (pin "24") (pinfunction "VDD_24") (pintype "unspecified"))
      (node (ref "U1") (pin "36") (pinfunction "VDD_36") (pintype "unspecified"))
      (node (ref "U1") (pin "48") (pinfunction "VDD_48") (pintype "unspecified"))
      (node (ref "U10") (pin "1") (pinfunction "VDD_1") (pintype "unspecified"))
      (node (ref "U11") (pin "1") (pinfunction "VDD_1") (pintype "unspecified"))
      (node (ref "U12") (pin "1") (pinfunction "VDD_1") (pintype "unspecified"))
      (node (ref "U13") (pin "1") (pinfunction "VDD_1") (pintype "unspecified"))
      (node (ref "U14") (pin "1") (pinfunction "VDD_1") (pintype "unspecified"))
      (node (ref "U15") (pin "1") (pinfunction "VDD_1") (pintype "unspecified"))
      (node (ref "U16") (pin "1") (pinfunction "VDD_1") (pintype "unspecified"))
      (node (ref "U17") (pin "1") (pinfunction "VDD_1") (pintype "unspecified"))
      (node (ref "U18") (pin "1") (pinfunction "VDD_1") (pintype "unspecified"))
      (node (ref "U19") (pin "1") (pinfunction "VDD_1") (pintype "unspecified"))
      (node (ref "U20") (pin "1") (pinfunction "VDD_1") (pintype "unspecified"))
      (node (ref "U21") (pin "1") (pinfunction "VDD_1") (pintype "unspecified"))
      (node (ref "U22") (pin "1") (pinfunction "VDD_1") (pintype "unspecified"))
      (node (ref "U23") (pin "1") (pinfunction "VDD_1") (pintype "unspecified"))
      (node (ref "U24") (pin "1") (pinfunction "VDD_1") (pintype "unspecified"))
      (node (ref "U4") (pin "2") (pinfunction "VOUT_2") (pintype "unspecified"))
      (node (ref "U4") (pin "4") (pinfunction "VOUT_4") (pintype "unspecified"))
      (node (ref "U9") (pin "1") (pinfunction "VDD_1") (pintype "unspecified"))
    )
    (net (code "2") (name "+3.3VA") (class "Default")
      (node (ref "C7") (pin "2") (pinfunction "2_2") (pintype "input"))
      (node (ref "C8") (pin "2") (pinfunction "2_2") (pintype "unspecified"))
      (node (ref "L1") (pin "2") (pinfunction "2_2") (pintype "unspecified"))
      (node (ref "U1") (pin "9") (pinfunction "VDDA/VREF+_9") (pintype "unspecified"))
    )
    (net (code "3") (name "+5V") (class "Default")
      (node (ref "C10") (pin "2") (pinfunction "2_2") (pintype "unspecified"))
      (node (ref "L2") (pin "2") (pinfunction "2_2") (pintype "unspecified"))
      (node (ref "U4") (pin "3") (pinfunction "VIN_3") (pintype "unspecified"))
    )
    (net (code "4") (name "AMUX_0") (class "Default")
      (node (ref "ADMUX_1") (pin "9") (pinfunction "I0_9") (pintype "unspecified"))
      (node (ref "C16") (pin "2") (pinfunction "2_2") (pintype "unspecified"))
      (node (ref "U9") (pin "3") (pinfunction "OUT_3") (pintype "unspecified"))
    )
    (net (code "5") (name "AMUX_1") (class "Default")
      (node (ref "ADMUX_1") (pin "8") (pinfunction "I1_8") (pintype "unspecified"))
      (node (ref "C18") (pin "2") (pinfunction "2_2") (pintype "unspecified"))
      (node (ref "U10") (pin "3") (pinfunction "OUT_3") (pintype "unspecified"))
    )
    (net (code "6") (name "AMUX_2") (class "Default")
      (node (ref "ADMUX_1") (pin "7") (pinfunction "I2_7") (pintype "unspecified"))
      (node (ref "C20") (pin "2") (pinfunction "2_2") (pintype "unspecified"))
      (node (ref "U11") (pin "3") (pinfunction "OUT_3") (pintype "unspecified"))
    )
    (net (code "7") (name "AMUX_3") (class "Default")
      (node (ref "ADMUX_1") (pin "6") (pinfunction "I3_6") (pintype "unspecified"))
      (node (ref "C22") (pin "2") (pinfunction "2_2") (pintype "unspecified"))
      (node (ref "U12") (pin "3") (pinfunction "OUT_3") (pintype "unspecified"))
    )
    (net (code "8") (name "AMUX_4") (class "Default")
      (node (ref "ADMUX_1") (pin "5") (pinfunction "I4_5") (pintype "unspecified"))
      (node (ref "C24") (pin "2") (pinfunction "2_2") (pintype "unspecified"))
      (node (ref "U13") (pin "3") (pinfunction "OUT_3") (pintype "unspecified"))
    )
    (net (code "9") (name "AMUX_5") (class "Default")
      (node (ref "ADMUX_1") (pin "4") (pinfunction "I5_4") (pintype "unspecified"))
      (node (ref "C26") (pin "2") (pinfunction "2_2") (pintype "unspecified"))
      (node (ref "U14") (pin "3") (pinfunction "OUT_3") (pintype "unspecified"))
    )
    (net (code "10") (name "AMUX_6") (class "Default")
      (node (ref "ADMUX_1") (pin "3") (pinfunction "I6_3") (pintype "unspecified"))
      (node (ref "C28") (pin "2") (pinfunction "2_2") (pintype "unspecified"))
      (node (ref "U15") (pin "3") (pinfunction "OUT_3") (pintype "unspecified"))
    )
    (net (code "11") (name "AMUX_7") (class "Default")
      (node (ref "ADMUX_1") (pin "2") (pinfunction "I7_2") (pintype "unspecified"))
      (node (ref "C30") (pin "2") (pinfunction "2_2") (pintype "unspecified"))
      (node (ref "U16") (pin "3") (pinfunction "OUT_3") (pintype "unspecified"))
    )
    (net (code "12") (name "AMUX_8") (class "Default")
      (node (ref "ADMUX_1") (pin "23") (pinfunction "I8_23") (pintype "unspecified"))
      (node (ref "C32") (pin "2") (pinfunction "2_2") (pintype "unspecified"))
      (node (ref "U17") (pin "3") (pinfunction "OUT_3") (pintype "unspecified"))
    )
    (net (code "13") (name "AMUX_9") (class "Default")
      (node (ref "ADMUX_1") (pin "22") (pinfunction "I9_22") (pintype "unspecified"))
      (node (ref "C34") (pin "2") (pinfunction "2_2") (pintype "unspecified"))
      (node (ref "U18") (pin "3") (pinfunction "OUT_3") (pintype "unspecified"))
    )
    (net (code "14") (name "AMUX_10") (class "Default")
      (node (ref "ADMUX_1") (pin "21") (pinfunction "I10_21") (pintype "unspecified"))
      (node (ref "C36") (pin "2") (pinfunction "2_2") (pintype "unspecified"))
      (node (ref "U19") (pin "3") (pinfunction "OUT_3") (pintype "unspecified"))
    )
    (net (code "15") (name "AMUX_11") (class "Default")
      (node (ref "ADMUX_1") (pin "20") (pinfunction "I11_20") (pintype "unspecified"))
      (node (ref "C38") (pin "2") (pinfunction "2_2") (pintype "unspecified"))
      (node (ref "U20") (pin "3") (pinfunction "OUT_3") (pintype "unspecified"))
    )
    (net (code "16") (name "AMUX_12") (class "Default")
      (node (ref "ADMUX_1") (pin "19") (pinfunction "I12_19") (pintype "unspecified"))
      (node (ref "C40") (pin "2") (pinfunction "2_2") (pintype "unspecified"))
      (node (ref "U21") (pin "3") (pinfunction "OUT_3") (pintype "unspecified"))
    )
    (net (code "17") (name "AMUX_13") (class "Default")
      (node (ref "ADMUX_1") (pin "18") (pinfunction "I13_18") (pintype "unspecified"))
      (node (ref "C42") (pin "2") (pinfunction "2_2") (pintype "unspecified"))
      (node (ref "U22") (pin "3") (pinfunction "OUT_3") (pintype "unspecified"))
    )
    (net (code "18") (name "AMUX_14") (class "Default")
      (node (ref "ADMUX_1") (pin "17") (pinfunction "I14_17") (pintype "unspecified"))
      (node (ref "C44") (pin "2") (pinfunction "2_2") (pintype "unspecified"))
      (node (ref "U23") (pin "3") (pinfunction "OUT_3") (pintype "unspecified"))
    )
    (net (code "19") (name "AMUX_15") (class "Default")
      (node (ref "ADMUX_1") (pin "16") (pinfunction "I15_16") (pintype "unspecified"))
      (node (ref "C46") (pin "2") (pinfunction "2_2") (pintype "unspecified"))
      (node (ref "U24") (pin "3") (pinfunction "OUT_3") (pintype "unspecified"))
    )
    (net (code "20") (name "AMUX_COM") (class "Default")
      (node (ref "ADMUX_1") (pin "1") (pinfunction "COMMON_INOUT/OUTPUT_1") (pintype "unspecified"))
      (node (ref "U1") (pin "13") (pinfunction "PA3_13") (pintype "unspecified"))
    )
    (net (code "21") (name "BOOT0") (class "Default")
      (node (ref "BOOT_BTN") (pin "2") (pinfunction "2_2") (pintype "input"))
      (node (ref "BOOT_BTN") (pin "4") (pinfunction "4_4") (pintype "input"))
      (node (ref "R5") (pin "1") (pinfunction "1_1") (pintype "unspecified"))
      (node (ref "U1") (pin "44") (pinfunction "BOOT0_44") (pintype "input"))
    )
    (net (code "22") (name "GND") (class "Default")
      (node (ref "ADMUX_1") (pin "12") (pinfunction "GND_12") (pintype "unspecified"))
      (node (ref "ADMUX_1") (pin "15") (pinfunction "E#_15") (pintype "unspecified"))
      (node (ref "C1") (pin "2") (pinfunction "2_2") (pintype "unspecified"))
      (node (ref "C10") (pin "1") (pinfunction "1_1") (pintype "unspecified"))
      (node (ref "C11") (pin "1") (pinfunction "1_1") (pintype "unspecified"))
      (node (ref "C12") (pin "2") (pinfunction "2_2") (pintype "unspecified"))
      (node (ref "C13") (pin "1") (pinfunction "1_1") (pintype "input"))
      (node (ref "C14") (pin "1") (pinfunction "1_1") (pintype "input"))
      (node (ref "C15") (pin "1") (pinfunction "1_1") (pintype "unspecified"))
      (node (ref "C16") (pin "1") (pinfunction "1_1") (pintype "unspecified"))
      (node (ref "C17") (pin "1") (pinfunction "1_1") (pintype "unspecified"))
      (node (ref "C18") (pin "1") (pinfunction "1_1") (pintype "unspecified"))
      (node (ref "C19") (pin "1") (pinfunction "1_1") (pintype "unspecified"))
      (node (ref "C2") (pin "2") (pinfunction "2_2") (pintype "unspecified"))
      (node (ref "C20") (pin "1") (pinfunction "1_1") (pintype "unspecified"))
      (node (ref "C21") (pin "1") (pinfunction "1_1") (pintype "unspecified"))
      (node (ref "C22") (pin "1") (pinfunction "1_1") (pintype "unspecified"))
      (node (ref "C23") (pin "1") (pinfunction "1_1") (pintype "unspecified"))
      (node (ref "C24") (pin "1") (pinfunction "1_1") (pintype "unspecified"))
      (node (ref "C25") (pin "1") (pinfunction "1_1") (pintype "unspecified"))
      (node (ref "C26") (pin "1") (pinfunction "1_1") (pintype "unspecified"))
      (node (ref "C27") (pin "1") (pinfunction "1_1") (pintype "unspecified"))
      (node (ref "C28") (pin "1") (pinfunction "1_1") (pintype "unspecified"))
      (node (ref "C29") (pin "1") (pinfunction "1_1") (pintype "unspecified"))
      (node (ref "C3") (pin "2") (pinfunction "2_2") (pintype "unspecified"))
      (node (ref "C30") (pin "1") (pinfunction "1_1") (pintype "unspecified"))
      (node (ref "C31") (pin "1") (pinfunction "1_1") (pintype "unspecified"))
      (node (ref "C32") (pin "1") (pinfunction "1_1") (pintype "unspecified"))
      (node (ref "C33") (pin "1") (pinfunction "1_1") (pintype "unspecified"))
      (node (ref "C34") (pin "1") (pinfunction "1_1") (pintype "unspecified"))
      (node (ref "C35") (pin "1") (pinfunction "1_1") (pintype "unspecified"))
      (node (ref "C36") (pin "1") (pinfunction "1_1") (pintype "unspecified"))
      (node (ref "C37") (pin "1") (pinfunction "1_1") (pintype "unspecified"))
      (node (ref "C38") (pin "1") (pinfunction "1_1") (pintype "unspecified"))
      (node (ref "C39") (pin "1") (pinfunction "1_1") (pintype "unspecified"))
      (node (ref "C4") (pin "2") (pinfunction "2_2") (pintype "unspecified"))
      (node (ref "C40") (pin "1") (pinfunction "1_1") (pintype "unspecified"))
      (node (ref "C41") (pin "1") (pinfunction "1_1") (pintype "unspecified"))
      (node (ref "C42") (pin "1") (pinfunction "1_1") (pintype "unspecified"))
      (node (ref "C43") (pin "1") (pinfunction "1_1") (pintype "unspecified"))
      (node (ref "C44") (pin "1") (pinfunction "1_1") (pintype "unspecified"))
      (node (ref "C45") (pin "1") (pinfunction "1_1") (pintype "unspecified"))
      (node (ref "C46") (pin "1") (pinfunction "1_1") (pintype "unspecified"))
      (node (ref "C5") (pin "2") (pinfunction "2_2") (pintype "unspecified"))
      (node (ref "C6") (pin "1") (pinfunction "1_1") (pintype "unspecified"))
      (node (ref "C7") (pin "1") (pinfunction "1_1") (pintype "input"))
      (node (ref "C8") (pin "1") (pinfunction "1_1") (pintype "unspecified"))
      (node (ref "C9") (pin "1") (pinfunction "1_1") (pintype "unspecified"))
      (node (ref "DEBUG") (pin "4") (pinfunction "4_4") (pintype "input"))
      (node (ref "I2C") (pin "4") (pinfunction "4_4") (pintype "input"))
      (node (ref "R1") (pin "1") (pinfunction "1_1") (pintype "unspecified"))
      (node (ref "R2") (pin "2") (pinfunction "2_2") (pintype "unspecified"))
      (node (ref "R3") (pin "1") (pinfunction "1_1") (pintype "unspecified"))
      (node (ref "R5") (pin "2") (pinfunction "2_2") (pintype "unspecified"))
      (node (ref "RST_BTN") (pin "2") (pinfunction "2_2") (pintype "input"))
      (node (ref "RST_BTN") (pin "4") (pinfunction "4_4") (pintype "input"))
      (node (ref "U1") (pin "23") (pinfunction "VSS_23") (pintype "unspecified"))
      (node (ref "U1") (pin "35") (pinfunction "VSS_35") (pintype "unspecified"))
      (node (ref "U1") (pin "47") (pinfunction "VSS_47") (pintype "unspecified"))
      (node (ref "U1") (pin "8") (pinfunction "VSSA/VREF-_8") (pintype "unspecified"))
      (node (ref "U10") (pin "5") (pinfunction "GND_5") (pintype "unspecified"))
      (node (ref "U10") (pin "7") (pinfunction "EP_7") (pintype "unspecified"))
      (node (ref "U11") (pin "5") (pinfunction "GND_5") (pintype "unspecified"))
      (node (ref "U11") (pin "7") (pinfunction "EP_7") (pintype "unspecified"))
      (node (ref "U12") (pin "5") (pinfunction "GND_5") (pintype "unspecified"))
      (node (ref "U12") (pin "7") (pinfunction "EP_7") (pintype "unspecified"))
      (node (ref "U13") (pin "5") (pinfunction "GND_5") (pintype "unspecified"))
      (node (ref "U13") (pin "7") (pinfunction "EP_7") (pintype "unspecified"))
      (node (ref "U14") (pin "5") (pinfunction "GND_5") (pintype "unspecified"))
      (node (ref "U14") (pin "7") (pinfunction "EP_7") (pintype "unspecified"))
      (node (ref "U15") (pin "5") (pinfunction "GND_5") (pintype "unspecified"))
      (node (ref "U15") (pin "7") (pinfunction "EP_7") (pintype "unspecified"))
      (node (ref "U16") (pin "5") (pinfunction "GND_5") (pintype "unspecified"))
      (node (ref "U16") (pin "7") (pinfunction "EP_7") (pintype "unspecified"))
      (node (ref "U17") (pin "5") (pinfunction "GND_5") (pintype "unspecified"))
      (node (ref "U17") (pin "7") (pinfunction "EP_7") (pintype "unspecified"))
      (node (ref "U18") (pin "5") (pinfunction "GND_5") (pintype "unspecified"))
      (node (ref "U18") (pin "7") (pinfunction "EP_7") (pintype "unspecified"))
      (node (ref "U19") (pin "5") (pinfunction "GND_5") (pintype "unspecified"))
      (node (ref "U19") (pin "7") (pinfunction "EP_7") (pintype "unspecified"))
      (node (ref "U20") (pin "5") (pinfunction "GND_5") (pintype "unspecified"))
      (node (ref "U20") (pin "7") (pinfunction "EP_7") (pintype "unspecified"))
      (node (ref "U21") (pin "5") (pinfunction "GND_5") (pintype "unspecified"))
      (node (ref "U21") (pin "7") (pinfunction "EP_7") (pintype "unspecified"))
      (node (ref "U22") (pin "5") (pinfunction "GND_5") (pintype "unspecified"))
      (node (ref "U22") (pin "7") (pinfunction "EP_7") (pintype "unspecified"))
      (node (ref "U23") (pin "5") (pinfunction "GND_5") (pintype "unspecified"))
      (node (ref "U23") (pin "7") (pinfunction "EP_7") (pintype "unspecified"))
      (node (ref "U24") (pin "5") (pinfunction "GND_5") (pintype "unspecified"))
      (node (ref "U24") (pin "7") (pinfunction "EP_7") (pintype "unspecified"))
      (node (ref "U4") (pin "1") (pinfunction "GND_1") (pintype "unspecified"))
      (node (ref "U9") (pin "5") (pinfunction "GND_5") (pintype "unspecified"))
      (node (ref "U9") (pin "7") (pinfunction "EP_7") (pintype "unspecified"))
      (node (ref "USB1") (pin "A1-B12") (pinfunction "GND_A1-B12") (pintype "unspecified"))
      (node (ref "USB1") (pin "B1-A12") (pinfunction "GND_B1-A12") (pintype "unspecified"))
      (node (ref "X5") (pin "2") (pinfunction "GND_2") (pintype "input"))
      (node (ref "X5") (pin "4") (pinfunction "GND_4") (pintype "input"))
    )
    (net (code "23") (name "HSE_IN") (class "Default")
      (node (ref "C14") (pin "2") (pinfunction "2_2") (pintype "input"))
      (node (ref "U1") (pin "5") (pinfunction "PH0-OSC_IN_5") (pintype "unspecified"))
      (node (ref "X5") (pin "1") (pinfunction "1_1") (pintype "input"))
    )
    (net (code "24") (name "HSE_OUT") (class "Default")
      (node (ref "C13") (pin "2") (pinfunction "2_2") (pintype "input"))
      (node (ref "U1") (pin "6") (pinfunction "PH1-OSC_OUT_6") (pintype "unspecified"))
      (node (ref "X5") (pin "3") (pinfunction "3_3") (pintype "input"))
    )
    (net (code "25") (name "NRST") (class "Default")
      (node (ref "C12") (pin "1") (pinfunction "1_1") (pintype "unspecified"))
      (node (ref "R4") (pin "2") (pinfunction "2_2") (pintype "unspecified"))
      (node (ref "RST_BTN") (pin "1") (pinfunction "1_1") (pintype "input"))
      (node (ref "RST_BTN") (pin "3") (pinfunction "3_3") (pintype "input"))
      (node (ref "U1") (pin "7") (pinfunction "NRST_7") (pintype "unspecified"))
    )
    (net (code "26") (name "Net-(LED1-K)") (class "Default")
      (node (ref "LED1") (pin "1") (pinfunction "K_1") (pintype "unspecified"))
      (node (ref "R3") (pin "2") (pinfunction "2_2") (pintype "unspecified"))
    )
    (net (code "27") (name "Net-(USB1-CC1)") (class "Default")
      (node (ref "R1") (pin "2") (pinfunction "2_2") (pintype "unspecified"))
      (node (ref "USB1") (pin "A5") (pinfunction "CC1_A5") (pintype "unspecified"))
    )
    (net (code "28") (name "Net-(USB1-CC2)") (class "Default")
      (node (ref "R2") (pin "1") (pinfunction "1_1") (pintype "unspecified"))
      (node (ref "USB1") (pin "B5") (pinfunction "CC2_B5") (pintype "unspecified"))
    )
    (net (code "29") (name "SCL") (class "Default")
      (node (ref "I2C") (pin "2") (pinfunction "2_2") (pintype "input"))
      (node (ref "R6") (pin "1") (pinfunction "1_1") (pintype "unspecified"))
      (node (ref "U1") (pin "42") (pinfunction "PB6_42") (pintype "unspecified"))
    )
    (net (code "30") (name "SDA") (class "Default")
      (node (ref "I2C") (pin "3") (pinfunction "3_3") (pintype "input"))
      (node (ref "R7") (pin "1") (pinfunction "1_1") (pintype "unspecified"))
      (node (ref "U1") (pin "43") (pinfunction "PB7_43") (pintype "unspecified"))
    )
    (net (code "31") (name "SEL0") (class "Default")
      (node (ref "ADMUX_1") (pin "10") (pinfunction "S0_10") (pintype "unspecified"))
      (node (ref "U1") (pin "25") (pinfunction "PB12_25") (pintype "unspecified"))
    )
    (net (code "32") (name "SEL1") (class "Default")
      (node (ref "ADMUX_1") (pin "11") (pinfunction "S1_11") (pintype "unspecified"))
      (node (ref "U1") (pin "26") (pinfunction "PB13_26") (pintype "unspecified"))
    )
    (net (code "33") (name "SEL2") (class "Default")
      (node (ref "ADMUX_1") (pin "14") (pinfunction "S2_14") (pintype "unspecified"))
      (node (ref "U1") (pin "27") (pinfunction "PB14_27") (pintype "unspecified"))
    )
    (net (code "34") (name "SEL3") (class "Default")
      (node (ref "ADMUX_1") (pin "13") (pinfunction "S3_13") (pintype "unspecified"))
      (node (ref "U1") (pin "28") (pinfunction "PB15_28") (pintype "unspecified"))
    )
    (net (code "35") (name "SWCLK") (class "Default")
      (node (ref "DEBUG") (pin "3") (pinfunction "3_3") (pintype "input"))
      (node (ref "U1") (pin "37") (pinfunction "PA14_37") (pintype "unspecified"))
    )
    (net (code "36") (name "SWDIO") (class "Default")
      (node (ref "DEBUG") (pin "2") (pinfunction "2_2") (pintype "input"))
      (node (ref "U1") (pin "34") (pinfunction "PA13_34") (pintype "unspecified"))
    )
    (net (code "37") (name "USB_DN") (class "Default")
      (node (ref "U1") (pin "32") (pinfunction "PA11_32") (pintype "unspecified"))
      (node (ref "USB1") (pin "A7") (pinfunction "DN1_A7") (pintype "unspecified"))
      (node (ref "USB1") (pin "B7") (pinfunction "DN2_B7") (pintype "unspecified"))
    )
    (net (code "38") (name "USB_DP") (class "Default")
      (node (ref "U1") (pin "33") (pinfunction "PA12_33") (pintype "unspecified"))
      (node (ref "USB1") (pin "A6") (pinfunction "DP1_A6") (pintype "unspecified"))
      (node (ref "USB1") (pin "B6") (pinfunction "DP2_B6") (pintype "unspecified"))
    )
    (net (code "39") (name "VBUS") (class "Default")
      (node (ref "L2") (pin "1") (pinfunction "1_1") (pintype "unspecified"))
      (node (ref "USB1") (pin "A4-B9") (pinfunction "VBUS_A4-B9") (pintype "unspecified"))
      (node (ref "USB1") (pin "B4-A9") (pinfunction "VBUS_B4-A9") (pintype "unspecified"))
    )
    (net (code "40") (name "unconnected-(U1-PA0-Pad10)") (class "Default")
      (node (ref "U1") (pin "10") (pinfunction "PA0_10") (pintype "unspecified+no_connect"))
    )
    (net (code "41") (name "unconnected-(U1-PA1-Pad11)") (class "Default")
      (node (ref "U1") (pin "11") (pinfunction "PA1_11") (pintype "unspecified+no_connect"))
    )
    (net (code "42") (name "unconnected-(U1-PA2-Pad12)") (class "Default")
      (node (ref "U1") (pin "12") (pinfunction "PA2_12") (pintype "unspecified+no_connect"))
    )
    (net (code "43") (name "unconnected-(U1-PA4-Pad14)") (class "Default")
      (node (ref "U1") (pin "14") (pinfunction "PA4_14") (pintype "unspecified+no_connect"))
    )
    (net (code "44") (name "unconnected-(U1-PA5-Pad15)") (class "Default")
      (node (ref "U1") (pin "15") (pinfunction "PA5_15") (pintype "unspecified+no_connect"))
    )
    (net (code "45") (name "unconnected-(U1-PA6-Pad16)") (class "Default")
      (node (ref "U1") (pin "16") (pinfunction "PA6_16") (pintype "unspecified+no_connect"))
    )
    (net (code "46") (name "unconnected-(U1-PA7-Pad17)") (class "Default")
      (node (ref "U1") (pin "17") (pinfunction "PA7_17") (pintype "unspecified+no_connect"))
    )
    (net (code "47") (name "unconnected-(U1-PA8-Pad29)") (class "Default")
      (node (ref "U1") (pin "29") (pinfunction "PA8_29") (pintype "unspecified+no_connect"))
    )
    (net (code "48") (name "unconnected-(U1-PA9-Pad30)") (class "Default")
      (node (ref "U1") (pin "30") (pinfunction "PA9_30") (pintype "unspecified+no_connect"))
    )
    (net (code "49") (name "unconnected-(U1-PA10-Pad31)") (class "Default")
      (node (ref "U1") (pin "31") (pinfunction "PA10_31") (pintype "unspecified+no_connect"))
    )
    (net (code "50") (name "unconnected-(U1-PA15-Pad38)") (class "Default")
      (node (ref "U1") (pin "38") (pinfunction "PA15_38") (pintype "unspecified+no_connect"))
    )
    (net (code "51") (name "unconnected-(U1-PAD-Pad49)") (class "Default")
      (node (ref "U1") (pin "49") (pinfunction "PAD_49") (pintype "unspecified+no_connect"))
    )
    (net (code "52") (name "unconnected-(U1-PB0-Pad18)") (class "Default")
      (node (ref "U1") (pin "18") (pinfunction "PB0_18") (pintype "unspecified+no_connect"))
    )
    (net (code "53") (name "unconnected-(U1-PB1-Pad19)") (class "Default")
      (node (ref "U1") (pin "19") (pinfunction "PB1_19") (pintype "unspecified+no_connect"))
    )
    (net (code "54") (name "unconnected-(U1-PB2-Pad20)") (class "Default")
      (node (ref "U1") (pin "20") (pinfunction "PB2_20") (pintype "unspecified+no_connect"))
    )
    (net (code "55") (name "unconnected-(U1-PB3-Pad39)") (class "Default")
      (node (ref "U1") (pin "39") (pinfunction "PB3_39") (pintype "unspecified+no_connect"))
    )
    (net (code "56") (name "unconnected-(U1-PB4-Pad40)") (class "Default")
      (node (ref "U1") (pin "40") (pinfunction "PB4_40") (pintype "unspecified+no_connect"))
    )
    (net (code "57") (name "unconnected-(U1-PB5-Pad41)") (class "Default")
      (node (ref "U1") (pin "41") (pinfunction "PB5_41") (pintype "unspecified+no_connect"))
    )
    (net (code "58") (name "unconnected-(U1-PB8-Pad45)") (class "Default")
      (node (ref "U1") (pin "45") (pinfunction "PB8_45") (pintype "unspecified+no_connect"))
    )
    (net (code "59") (name "unconnected-(U1-PB9-Pad46)") (class "Default")
      (node (ref "U1") (pin "46") (pinfunction "PB9_46") (pintype "unspecified+no_connect"))
    )
    (net (code "60") (name "unconnected-(U1-PB10-Pad21)") (class "Default")
      (node (ref "U1") (pin "21") (pinfunction "PB10_21") (pintype "unspecified+no_connect"))
    )
    (net (code "61") (name "unconnected-(U1-PC13-Pad2)") (class "Default")
      (node (ref "U1") (pin "2") (pinfunction "PC13_2") (pintype "unspecified+no_connect"))
    )
    (net (code "62") (name "unconnected-(U1-PC14{slash}OSC32IN-Pad3)") (class "Default")
      (node (ref "U1") (pin "3") (pinfunction "PC14/OSC32IN_3") (pintype "unspecified+no_connect"))
    )
    (net (code "63") (name "unconnected-(U1-PC15{slash}OSC32OUT-Pad4)") (class "Default")
      (node (ref "U1") (pin "4") (pinfunction "PC15/OSC32OUT_4") (pintype "unspecified+no_connect"))
    )
    (net (code "64") (name "unconnected-(U1-VCAP1-Pad22)") (class "Default")
      (node (ref "U1") (pin "22") (pinfunction "VCAP1_22") (pintype "unspecified+no_connect"))
    )
    (net (code "65") (name "unconnected-(U9-NC-Pad2)") (class "Default")
      (node (ref "U9") (pin "2") (pinfunction "NC_2") (pintype "unspecified+no_connect"))
    )
    (net (code "66") (name "unconnected-(U9-NC-Pad4)") (class "Default")
      (node (ref "U9") (pin "4") (pinfunction "NC_4") (pintype "unspecified+no_connect"))
    )
    (net (code "67") (name "unconnected-(U9-NC-Pad6)") (class "Default")
      (node (ref "U9") (pin "6") (pinfunction "NC_6") (pintype "unspecified+no_connect"))
    )
    (net (code "68") (name "unconnected-(U10-NC-Pad2)") (class "Default")
      (node (ref "U10") (pin "2") (pinfunction "NC_2") (pintype "unspecified+no_connect"))
    )
    (net (code "69") (name "unconnected-(U10-NC-Pad4)") (class "Default")
      (node (ref "U10") (pin "4") (pinfunction "NC_4") (pintype "unspecified+no_connect"))
    )
    (net (code "70") (name "unconnected-(U10-NC-Pad6)") (class "Default")
      (node (ref "U10") (pin "6") (pinfunction "NC_6") (pintype "unspecified+no_connect"))
    )
    (net (code "71") (name "unconnected-(U11-NC-Pad2)") (class "Default")
      (node (ref "U11") (pin "2") (pinfunction "NC_2") (pintype "unspecified+no_connect"))
    )
    (net (code "72") (name "unconnected-(U11-NC-Pad4)") (class "Default")
      (node (ref "U11") (pin "4") (pinfunction "NC_4") (pintype "unspecified+no_connect"))
    )
    (net (code "73") (name "unconnected-(U11-NC-Pad6)") (class "Default")
      (node (ref "U11") (pin "6") (pinfunction "NC_6") (pintype "unspecified+no_connect"))
    )
    (net (code "74") (name "unconnected-(U12-NC-Pad2)") (class "Default")
      (node (ref "U12") (pin "2") (pinfunction "NC_2") (pintype "unspecified+no_connect"))
    )
    (net (code "75") (name "unconnected-(U12-NC-Pad4)") (class "Default")
      (node (ref "U12") (pin "4") (pinfunction "NC_4") (pintype "unspecified+no_connect"))
    )
    (net (code "76") (name "unconnected-(U12-NC-Pad6)") (class "Default")
      (node (ref "U12") (pin "6") (pinfunction "NC_6") (pintype "unspecified+no_connect"))
    )
    (net (code "77") (name "unconnected-(U13-NC-Pad2)") (class "Default")
      (node (ref "U13") (pin "2") (pinfunction "NC_2") (pintype "unspecified+no_connect"))
    )
    (net (code "78") (name "unconnected-(U13-NC-Pad4)") (class "Default")
      (node (ref "U13") (pin "4") (pinfunction "NC_4") (pintype "unspecified+no_connect"))
    )
    (net (code "79") (name "unconnected-(U13-NC-Pad6)") (class "Default")
      (node (ref "U13") (pin "6") (pinfunction "NC_6") (pintype "unspecified+no_connect"))
    )
    (net (code "80") (name "unconnected-(U14-NC-Pad2)") (class "Default")
      (node (ref "U14") (pin "2") (pinfunction "NC_2") (pintype "unspecified+no_connect"))
    )
    (net (code "81") (name "unconnected-(U14-NC-Pad4)") (class "Default")
      (node (ref "U14") (pin "4") (pinfunction "NC_4") (pintype "unspecified+no_connect"))
    )
    (net (code "82") (name "unconnected-(U14-NC-Pad6)") (class "Default")
      (node (ref "U14") (pin "6") (pinfunction "NC_6") (pintype "unspecified+no_connect"))
    )
    (net (code "83") (name "unconnected-(U15-NC-Pad2)") (class "Default")
      (node (ref "U15") (pin "2") (pinfunction "NC_2") (pintype "unspecified+no_connect"))
    )
    (net (code "84") (name "unconnected-(U15-NC-Pad4)") (class "Default")
      (node (ref "U15") (pin "4") (pinfunction "NC_4") (pintype "unspecified+no_connect"))
    )
    (net (code "85") (name "unconnected-(U15-NC-Pad6)") (class "Default")
      (node (ref "U15") (pin "6") (pinfunction "NC_6") (pintype "unspecified+no_connect"))
    )
    (net (code "86") (name "unconnected-(U16-NC-Pad2)") (class "Default")
      (node (ref "U16") (pin "2") (pinfunction "NC_2") (pintype "unspecified+no_connect"))
    )
    (net (code "87") (name "unconnected-(U16-NC-Pad4)") (class "Default")
      (node (ref "U16") (pin "4") (pinfunction "NC_4") (pintype "unspecified+no_connect"))
    )
    (net (code "88") (name "unconnected-(U16-NC-Pad6)") (class "Default")
      (node (ref "U16") (pin "6") (pinfunction "NC_6") (pintype "unspecified+no_connect"))
    )
    (net (code "89") (name "unconnected-(U17-NC-Pad2)") (class "Default")
      (node (ref "U17") (pin "2") (pinfunction "NC_2") (pintype "unspecified+no_connect"))
    )
    (net (code "90") (name "unconnected-(U17-NC-Pad4)") (class "Default")
      (node (ref "U17") (pin "4") (pinfunction "NC_4") (pintype "unspecified+no_connect"))
    )
    (net (code "91") (name "unconnected-(U17-NC-Pad6)") (class "Default")
      (node (ref "U17") (pin "6") (pinfunction "NC_6") (pintype "unspecified+no_connect"))
    )
    (net (code "92") (name "unconnected-(U18-NC-Pad2)") (class "Default")
      (node (ref "U18") (pin "2") (pinfunction "NC_2") (pintype "unspecified+no_connect"))
    )
    (net (code "93") (name "unconnected-(U18-NC-Pad4)") (class "Default")
      (node (ref "U18") (pin "4") (pinfunction "NC_4") (pintype "unspecified+no_connect"))
    )
    (net (code "94") (name "unconnected-(U18-NC-Pad6)") (class "Default")
      (node (ref "U18") (pin "6") (pinfunction "NC_6") (pintype "unspecified+no_connect"))
    )
    (net (code "95") (name "unconnected-(U19-NC-Pad2)") (class "Default")
      (node (ref "U19") (pin "2") (pinfunction "NC_2") (pintype "unspecified+no_connect"))
    )
    (net (code "96") (name "unconnected-(U19-NC-Pad4)") (class "Default")
      (node (ref "U19") (pin "4") (pinfunction "NC_4") (pintype "unspecified+no_connect"))
    )
    (net (code "97") (name "unconnected-(U19-NC-Pad6)") (class "Default")
      (node (ref "U19") (pin "6") (pinfunction "NC_6") (pintype "unspecified+no_connect"))
    )
    (net (code "98") (name "unconnected-(U20-NC-Pad2)") (class "Default")
      (node (ref "U20") (pin "2") (pinfunction "NC_2") (pintype "unspecified+no_connect"))
    )
    (net (code "99") (name "unconnected-(U20-NC-Pad4)") (class "Default")
      (node (ref "U20") (pin "4") (pinfunction "NC_4") (pintype "unspecified+no_connect"))
    )
    (net (code "100") (name "unconnected-(U20-NC-Pad6)") (class "Default")
      (node (ref "U20") (pin "6") (pinfunction "NC_6") (pintype "unspecified+no_connect"))
    )
    (net (code "101") (name "unconnected-(U21-NC-Pad2)") (class "Default")
      (node (ref "U21") (pin "2") (pinfunction "NC_2") (pintype "unspecified+no_connect"))
    )
    (net (code "102") (name "unconnected-(U21-NC-Pad4)") (class "Default")
      (node (ref "U21") (pin "4") (pinfunction "NC_4") (pintype "unspecified+no_connect"))
    )
    (net (code "103") (name "unconnected-(U21-NC-Pad6)") (class "Default")
      (node (ref "U21") (pin "6") (pinfunction "NC_6") (pintype "unspecified+no_connect"))
    )
    (net (code "104") (name "unconnected-(U22-NC-Pad2)") (class "Default")
      (node (ref "U22") (pin "2") (pinfunction "NC_2") (pintype "unspecified+no_connect"))
    )
    (net (code "105") (name "unconnected-(U22-NC-Pad4)") (class "Default")
      (node (ref "U22") (pin "4") (pinfunction "NC_4") (pintype "unspecified+no_connect"))
    )
    (net (code "106") (name "unconnected-(U22-NC-Pad6)") (class "Default")
      (node (ref "U22") (pin "6") (pinfunction "NC_6") (pintype "unspecified+no_connect"))
    )
    (net (code "107") (name "unconnected-(U23-NC-Pad2)") (class "Default")
      (node (ref "U23") (pin "2") (pinfunction "NC_2") (pintype "unspecified+no_connect"))
    )
    (net (code "108") (name "unconnected-(U23-NC-Pad4)") (class "Default")
      (node (ref "U23") (pin "4") (pinfunction "NC_4") (pintype "unspecified+no_connect"))
    )
    (net (code "109") (name "unconnected-(U23-NC-Pad6)") (class "Default")
      (node (ref "U23") (pin "6") (pinfunction "NC_6") (pintype "unspecified+no_connect"))
    )
    (net (code "110") (name "unconnected-(U24-NC-Pad2)") (class "Default")
      (node (ref "U24") (pin "2") (pinfunction "NC_2") (pintype "unspecified+no_connect"))
    )
    (net (code "111") (name "unconnected-(U24-NC-Pad4)") (class "Default")
      (node (ref "U24") (pin "4") (pinfunction "NC_4") (pintype "unspecified+no_connect"))
    )
    (net (code "112") (name "unconnected-(U24-NC-Pad6)") (class "Default")
      (node (ref "U24") (pin "6") (pinfunction "NC_6") (pintype "unspecified+no_connect"))
    )
    (net (code "113") (name "unconnected-(USB1-EH-Pad1)") (class "Default")
      (node (ref "USB1") (pin "1") (pinfunction "EH_1") (pintype "unspecified+no_connect"))
    )
    (net (code "114") (name "unconnected-(USB1-EH-Pad2)") (class "Default")
      (node (ref "USB1") (pin "2") (pinfunction "EH_2") (pintype "unspecified+no_connect"))
    )
    (net (code "115") (name "unconnected-(USB1-EH-Pad3)") (class "Default")
      (node (ref "USB1") (pin "3") (pinfunction "EH_3") (pintype "unspecified+no_connect"))
    )
    (net (code "116") (name "unconnected-(USB1-EH-Pad4)") (class "Default")
      (node (ref "USB1") (pin "4") (pinfunction "EH_4") (pintype "unspecified+no_connect"))
    )
    (net (code "117") (name "unconnected-(USB1-SBU1-PadA8)") (class "Default")
      (node (ref "USB1") (pin "A8") (pinfunction "SBU1_A8") (pintype "unspecified+no_connect"))
    )
    (net (code "118") (name "unconnected-(USB1-SBU2-PadB8)") (class "Default")
      (node (ref "USB1") (pin "B8") (pinfunction "SBU2_B8") (pintype "unspecified+no_connect"))
    )
  )
)
